# LEDs.net
KiCad netlist of a schematic drawn in Altium Designer
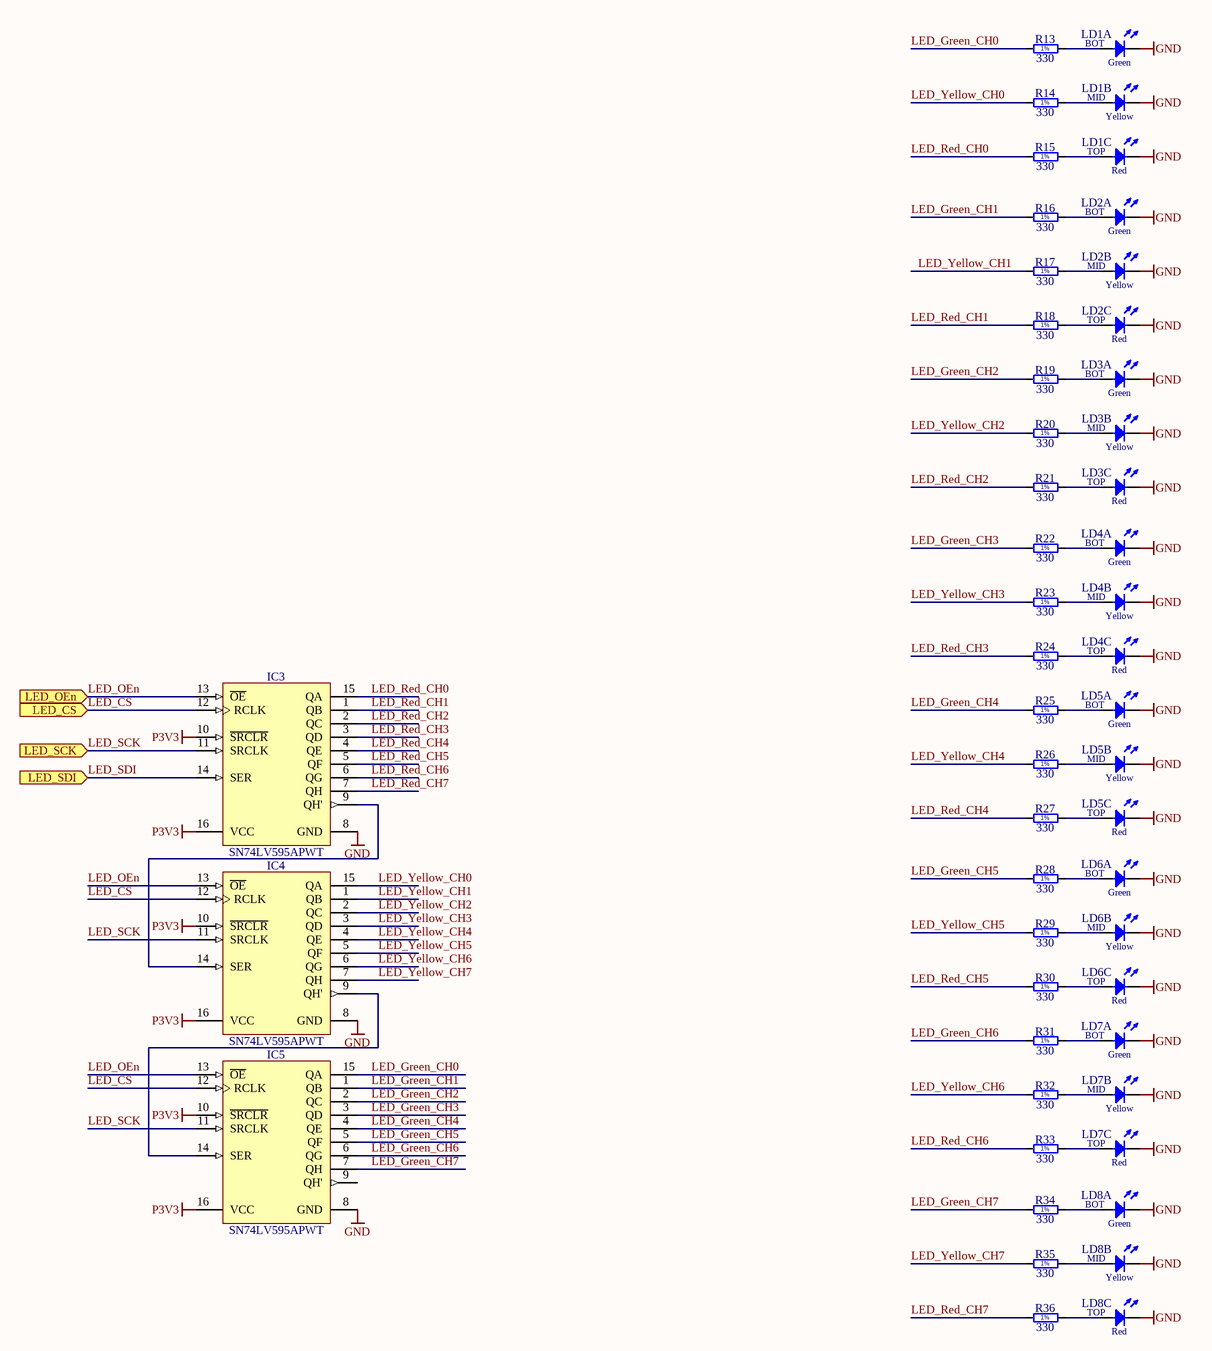
[diagram p0: LEDs.SchDoc]

(export (version "E")
  (design (tool "Eeschema 10.0.6"))
  (components
    (comp (ref "IC3")
      (value "SN74LV595APWT")
      (footprint "SOP65P640X120-16N")
      (description "8-Bit Shift Register With 3-State Output Register")
      (fields (field (name "MANUFACTURER") "TEXAS INSTRUMENTS") (field (name "AUTHOR") "CERN DEM JLC"))
      (libsource (lib "ICs And Semiconductors") (part "74595"))
    )
    (comp (ref "IC4")
      (value "SN74LV595APWT")
      (footprint "SOP65P640X120-16N")
      (description "8-Bit Shift Register With 3-State Output Register")
      (fields (field (name "MANUFACTURER") "TEXAS INSTRUMENTS") (field (name "AUTHOR") "CERN DEM JLC"))
      (libsource (lib "ICs And Semiconductors") (part "74595"))
    )
    (comp (ref "IC5")
      (value "SN74LV595APWT")
      (footprint "SOP65P640X120-16N")
      (description "8-Bit Shift Register With 3-State Output Register")
      (fields (field (name "MANUFACTURER") "TEXAS INSTRUMENTS") (field (name "AUTHOR") "CERN DEM JLC"))
      (libsource (lib "ICs And Semiconductors") (part "74595"))
    )
    (comp (ref "LD1")
      (value "Red/Yellow/Green")
      (footprint "LED_MENTOR_1882.2781")
      (description "LED x3 G-1C2A-BOT_Y-3C4A_R-5C6A-TOP")
      (fields
        (field (name "PART NUMBER") "LED_MENTOR_1882.2781")
        (field (name "MANUFACTURER") "MENTOR")
        (field (name "AUTHOR") "CERN DEM JLC")
      )
      (libsource (lib "ICs And Semiconductors") (part "LED x3 G-1C2A-BOT_Y-3C4A_R-5C6A-TOP"))
    )
    (comp (ref "LD2")
      (value "Red/Yellow/Green")
      (footprint "LED_MENTOR_1882.2781")
      (description "LED x3 G-1C2A-BOT_Y-3C4A_R-5C6A-TOP")
      (fields
        (field (name "PART NUMBER") "LED_MENTOR_1882.2781")
        (field (name "MANUFACTURER") "MENTOR")
        (field (name "AUTHOR") "CERN DEM JLC")
      )
      (libsource (lib "ICs And Semiconductors") (part "LED x3 G-1C2A-BOT_Y-3C4A_R-5C6A-TOP"))
    )
    (comp (ref "LD3")
      (value "Red/Yellow/Green")
      (footprint "LED_MENTOR_1882.2781")
      (description "LED x3 G-1C2A-BOT_Y-3C4A_R-5C6A-TOP")
      (fields
        (field (name "PART NUMBER") "LED_MENTOR_1882.2781")
        (field (name "MANUFACTURER") "MENTOR")
        (field (name "AUTHOR") "CERN DEM JLC")
      )
      (libsource (lib "ICs And Semiconductors") (part "LED x3 G-1C2A-BOT_Y-3C4A_R-5C6A-TOP"))
    )
    (comp (ref "LD4")
      (value "Red/Yellow/Green")
      (footprint "LED_MENTOR_1882.2781")
      (description "LED x3 G-1C2A-BOT_Y-3C4A_R-5C6A-TOP")
      (fields
        (field (name "PART NUMBER") "LED_MENTOR_1882.2781")
        (field (name "MANUFACTURER") "MENTOR")
        (field (name "AUTHOR") "CERN DEM JLC")
      )
      (libsource (lib "ICs And Semiconductors") (part "LED x3 G-1C2A-BOT_Y-3C4A_R-5C6A-TOP"))
    )
    (comp (ref "LD5")
      (value "Red/Yellow/Green")
      (footprint "LED_MENTOR_1882.2781")
      (description "LED x3 G-1C2A-BOT_Y-3C4A_R-5C6A-TOP")
      (fields
        (field (name "PART NUMBER") "LED_MENTOR_1882.2781")
        (field (name "MANUFACTURER") "MENTOR")
        (field (name "AUTHOR") "CERN DEM JLC")
      )
      (libsource (lib "ICs And Semiconductors") (part "LED x3 G-1C2A-BOT_Y-3C4A_R-5C6A-TOP"))
    )
    (comp (ref "LD6")
      (value "Red/Yellow/Green")
      (footprint "LED_MENTOR_1882.2781")
      (description "LED x3 G-1C2A-BOT_Y-3C4A_R-5C6A-TOP")
      (fields
        (field (name "PART NUMBER") "LED_MENTOR_1882.2781")
        (field (name "MANUFACTURER") "MENTOR")
        (field (name "AUTHOR") "CERN DEM JLC")
      )
      (libsource (lib "ICs And Semiconductors") (part "LED x3 G-1C2A-BOT_Y-3C4A_R-5C6A-TOP"))
    )
    (comp (ref "LD7")
      (value "Red/Yellow/Green")
      (footprint "LED_MENTOR_1882.2781")
      (description "LED x3 G-1C2A-BOT_Y-3C4A_R-5C6A-TOP")
      (fields
        (field (name "PART NUMBER") "LED_MENTOR_1882.2781")
        (field (name "MANUFACTURER") "MENTOR")
        (field (name "AUTHOR") "CERN DEM JLC")
      )
      (libsource (lib "ICs And Semiconductors") (part "LED x3 G-1C2A-BOT_Y-3C4A_R-5C6A-TOP"))
    )
    (comp (ref "LD8")
      (value "Red/Yellow/Green")
      (footprint "LED_MENTOR_1882.2781")
      (description "LED x3 G-1C2A-BOT_Y-3C4A_R-5C6A-TOP")
      (fields
        (field (name "PART NUMBER") "LED_MENTOR_1882.2781")
        (field (name "MANUFACTURER") "MENTOR")
        (field (name "AUTHOR") "CERN DEM JLC")
      )
      (libsource (lib "ICs And Semiconductors") (part "LED x3 G-1C2A-BOT_Y-3C4A_R-5C6A-TOP"))
    )
    (comp (ref "R13")
      (value "330")
      (footprint "RESC1608X55N")
      (description "Resistor - 1%")
      (fields
        (field (name "PART NUMBER") "R0603_330R_1%_0.1W_100PPM")
        (field (name "POWER") "0.1W")
        (field (name "AUTHOR") "CERN DEM JLC")
      )
      (libsource (lib "Resistors") (part "Resistor - 1%"))
    )
    (comp (ref "R14")
      (value "330")
      (footprint "RESC1608X55N")
      (description "Resistor - 1%")
      (fields
        (field (name "PART NUMBER") "R0603_330R_1%_0.1W_100PPM")
        (field (name "POWER") "0.1W")
        (field (name "AUTHOR") "CERN DEM JLC")
      )
      (libsource (lib "Resistors") (part "Resistor - 1%"))
    )
    (comp (ref "R15")
      (value "330")
      (footprint "RESC1608X55N")
      (description "Resistor - 1%")
      (fields
        (field (name "PART NUMBER") "R0603_330R_1%_0.1W_100PPM")
        (field (name "POWER") "0.1W")
        (field (name "AUTHOR") "CERN DEM JLC")
      )
      (libsource (lib "Resistors") (part "Resistor - 1%"))
    )
    (comp (ref "R16")
      (value "330")
      (footprint "RESC1608X55N")
      (description "Resistor - 1%")
      (fields
        (field (name "PART NUMBER") "R0603_330R_1%_0.1W_100PPM")
        (field (name "POWER") "0.1W")
        (field (name "AUTHOR") "CERN DEM JLC")
      )
      (libsource (lib "Resistors") (part "Resistor - 1%"))
    )
    (comp (ref "R17")
      (value "330")
      (footprint "RESC1608X55N")
      (description "Resistor - 1%")
      (fields
        (field (name "PART NUMBER") "R0603_330R_1%_0.1W_100PPM")
        (field (name "POWER") "0.1W")
        (field (name "AUTHOR") "CERN DEM JLC")
      )
      (libsource (lib "Resistors") (part "Resistor - 1%"))
    )
    (comp (ref "R18")
      (value "330")
      (footprint "RESC1608X55N")
      (description "Resistor - 1%")
      (fields
        (field (name "PART NUMBER") "R0603_330R_1%_0.1W_100PPM")
        (field (name "POWER") "0.1W")
        (field (name "AUTHOR") "CERN DEM JLC")
      )
      (libsource (lib "Resistors") (part "Resistor - 1%"))
    )
    (comp (ref "R19")
      (value "330")
      (footprint "RESC1608X55N")
      (description "Resistor - 1%")
      (fields
        (field (name "PART NUMBER") "R0603_330R_1%_0.1W_100PPM")
        (field (name "POWER") "0.1W")
        (field (name "AUTHOR") "CERN DEM JLC")
      )
      (libsource (lib "Resistors") (part "Resistor - 1%"))
    )
    (comp (ref "R20")
      (value "330")
      (footprint "RESC1608X55N")
      (description "Resistor - 1%")
      (fields
        (field (name "PART NUMBER") "R0603_330R_1%_0.1W_100PPM")
        (field (name "POWER") "0.1W")
        (field (name "AUTHOR") "CERN DEM JLC")
      )
      (libsource (lib "Resistors") (part "Resistor - 1%"))
    )
    (comp (ref "R21")
      (value "330")
      (footprint "RESC1608X55N")
      (description "Resistor - 1%")
      (fields
        (field (name "PART NUMBER") "R0603_330R_1%_0.1W_100PPM")
        (field (name "POWER") "0.1W")
        (field (name "AUTHOR") "CERN DEM JLC")
      )
      (libsource (lib "Resistors") (part "Resistor - 1%"))
    )
    (comp (ref "R22")
      (value "330")
      (footprint "RESC1608X55N")
      (description "Resistor - 1%")
      (fields
        (field (name "PART NUMBER") "R0603_330R_1%_0.1W_100PPM")
        (field (name "POWER") "0.1W")
        (field (name "AUTHOR") "CERN DEM JLC")
      )
      (libsource (lib "Resistors") (part "Resistor - 1%"))
    )
    (comp (ref "R23")
      (value "330")
      (footprint "RESC1608X55N")
      (description "Resistor - 1%")
      (fields
        (field (name "PART NUMBER") "R0603_330R_1%_0.1W_100PPM")
        (field (name "POWER") "0.1W")
        (field (name "AUTHOR") "CERN DEM JLC")
      )
      (libsource (lib "Resistors") (part "Resistor - 1%"))
    )
    (comp (ref "R24")
      (value "330")
      (footprint "RESC1608X55N")
      (description "Resistor - 1%")
      (fields
        (field (name "PART NUMBER") "R0603_330R_1%_0.1W_100PPM")
        (field (name "POWER") "0.1W")
        (field (name "AUTHOR") "CERN DEM JLC")
      )
      (libsource (lib "Resistors") (part "Resistor - 1%"))
    )
    (comp (ref "R25")
      (value "330")
      (footprint "RESC1608X55N")
      (description "Resistor - 1%")
      (fields
        (field (name "PART NUMBER") "R0603_330R_1%_0.1W_100PPM")
        (field (name "POWER") "0.1W")
        (field (name "AUTHOR") "CERN DEM JLC")
      )
      (libsource (lib "Resistors") (part "Resistor - 1%"))
    )
    (comp (ref "R26")
      (value "330")
      (footprint "RESC1608X55N")
      (description "Resistor - 1%")
      (fields
        (field (name "PART NUMBER") "R0603_330R_1%_0.1W_100PPM")
        (field (name "POWER") "0.1W")
        (field (name "AUTHOR") "CERN DEM JLC")
      )
      (libsource (lib "Resistors") (part "Resistor - 1%"))
    )
    (comp (ref "R27")
      (value "330")
      (footprint "RESC1608X55N")
      (description "Resistor - 1%")
      (fields
        (field (name "PART NUMBER") "R0603_330R_1%_0.1W_100PPM")
        (field (name "POWER") "0.1W")
        (field (name "AUTHOR") "CERN DEM JLC")
      )
      (libsource (lib "Resistors") (part "Resistor - 1%"))
    )
    (comp (ref "R28")
      (value "330")
      (footprint "RESC1608X55N")
      (description "Resistor - 1%")
      (fields
        (field (name "PART NUMBER") "R0603_330R_1%_0.1W_100PPM")
        (field (name "POWER") "0.1W")
        (field (name "AUTHOR") "CERN DEM JLC")
      )
      (libsource (lib "Resistors") (part "Resistor - 1%"))
    )
    (comp (ref "R29")
      (value "330")
      (footprint "RESC1608X55N")
      (description "Resistor - 1%")
      (fields
        (field (name "PART NUMBER") "R0603_330R_1%_0.1W_100PPM")
        (field (name "POWER") "0.1W")
        (field (name "AUTHOR") "CERN DEM JLC")
      )
      (libsource (lib "Resistors") (part "Resistor - 1%"))
    )
    (comp (ref "R30")
      (value "330")
      (footprint "RESC1608X55N")
      (description "Resistor - 1%")
      (fields
        (field (name "PART NUMBER") "R0603_330R_1%_0.1W_100PPM")
        (field (name "POWER") "0.1W")
        (field (name "AUTHOR") "CERN DEM JLC")
      )
      (libsource (lib "Resistors") (part "Resistor - 1%"))
    )
    (comp (ref "R31")
      (value "330")
      (footprint "RESC1608X55N")
      (description "Resistor - 1%")
      (fields
        (field (name "PART NUMBER") "R0603_330R_1%_0.1W_100PPM")
        (field (name "POWER") "0.1W")
        (field (name "AUTHOR") "CERN DEM JLC")
      )
      (libsource (lib "Resistors") (part "Resistor - 1%"))
    )
    (comp (ref "R32")
      (value "330")
      (footprint "RESC1608X55N")
      (description "Resistor - 1%")
      (fields
        (field (name "PART NUMBER") "R0603_330R_1%_0.1W_100PPM")
        (field (name "POWER") "0.1W")
        (field (name "AUTHOR") "CERN DEM JLC")
      )
      (libsource (lib "Resistors") (part "Resistor - 1%"))
    )
    (comp (ref "R33")
      (value "330")
      (footprint "RESC1608X55N")
      (description "Resistor - 1%")
      (fields
        (field (name "PART NUMBER") "R0603_330R_1%_0.1W_100PPM")
        (field (name "POWER") "0.1W")
        (field (name "AUTHOR") "CERN DEM JLC")
      )
      (libsource (lib "Resistors") (part "Resistor - 1%"))
    )
    (comp (ref "R34")
      (value "330")
      (footprint "RESC1608X55N")
      (description "Resistor - 1%")
      (fields
        (field (name "PART NUMBER") "R0603_330R_1%_0.1W_100PPM")
        (field (name "POWER") "0.1W")
        (field (name "AUTHOR") "CERN DEM JLC")
      )
      (libsource (lib "Resistors") (part "Resistor - 1%"))
    )
    (comp (ref "R35")
      (value "330")
      (footprint "RESC1608X55N")
      (description "Resistor - 1%")
      (fields
        (field (name "PART NUMBER") "R0603_330R_1%_0.1W_100PPM")
        (field (name "POWER") "0.1W")
        (field (name "AUTHOR") "CERN DEM JLC")
      )
      (libsource (lib "Resistors") (part "Resistor - 1%"))
    )
    (comp (ref "R36")
      (value "330")
      (footprint "RESC1608X55N")
      (description "Resistor - 1%")
      (fields
        (field (name "PART NUMBER") "R0603_330R_1%_0.1W_100PPM")
        (field (name "POWER") "0.1W")
        (field (name "AUTHOR") "CERN DEM JLC")
      )
      (libsource (lib "Resistors") (part "Resistor - 1%"))
    )
  )
  (nets
    (net (code "1") (name "/LED_CS") (class "Default")
      (node (ref "IC3") (pin "12") (pinfunction "RCLK_12") (pintype "input"))
      (node (ref "IC4") (pin "12") (pinfunction "RCLK_12") (pintype "input"))
      (node (ref "IC5") (pin "12") (pinfunction "RCLK_12") (pintype "input"))
    )
    (net (code "2") (name "/LED_Green_CH0") (class "Default")
      (node (ref "IC5") (pin "15") (pinfunction "QA_15") (pintype "tri_state"))
      (node (ref "R13") (pin "1") (pinfunction "1_1") (pintype "passive"))
    )
    (net (code "3") (name "/LED_Green_CH1") (class "Default")
      (node (ref "IC5") (pin "1") (pinfunction "QB_1") (pintype "tri_state"))
      (node (ref "R16") (pin "1") (pinfunction "1_1") (pintype "passive"))
    )
    (net (code "4") (name "/LED_Green_CH2") (class "Default")
      (node (ref "IC5") (pin "2") (pinfunction "QC_2") (pintype "tri_state"))
      (node (ref "R19") (pin "1") (pinfunction "1_1") (pintype "passive"))
    )
    (net (code "5") (name "/LED_Green_CH3") (class "Default")
      (node (ref "IC5") (pin "3") (pinfunction "QD_3") (pintype "tri_state"))
      (node (ref "R22") (pin "1") (pinfunction "1_1") (pintype "passive"))
    )
    (net (code "6") (name "/LED_Green_CH4") (class "Default")
      (node (ref "IC5") (pin "4") (pinfunction "QE_4") (pintype "tri_state"))
      (node (ref "R25") (pin "1") (pinfunction "1_1") (pintype "passive"))
    )
    (net (code "7") (name "/LED_Green_CH5") (class "Default")
      (node (ref "IC5") (pin "5") (pinfunction "QF_5") (pintype "tri_state"))
      (node (ref "R28") (pin "1") (pinfunction "1_1") (pintype "passive"))
    )
    (net (code "8") (name "/LED_Green_CH6") (class "Default")
      (node (ref "IC5") (pin "6") (pinfunction "QG_6") (pintype "tri_state"))
      (node (ref "R31") (pin "1") (pinfunction "1_1") (pintype "passive"))
    )
    (net (code "9") (name "/LED_Green_CH7") (class "Default")
      (node (ref "IC5") (pin "7") (pinfunction "QH_7") (pintype "tri_state"))
      (node (ref "R34") (pin "1") (pinfunction "1_1") (pintype "passive"))
    )
    (net (code "10") (name "/LED_OEn") (class "Default")
      (node (ref "IC3") (pin "13") (pinfunction "~{OE}_13") (pintype "input"))
      (node (ref "IC4") (pin "13") (pinfunction "~{OE}_13") (pintype "input"))
      (node (ref "IC5") (pin "13") (pinfunction "~{OE}_13") (pintype "input"))
    )
    (net (code "11") (name "/LED_Red_CH0") (class "Default")
      (node (ref "IC3") (pin "15") (pinfunction "QA_15") (pintype "tri_state"))
      (node (ref "R15") (pin "1") (pinfunction "1_1") (pintype "passive"))
    )
    (net (code "12") (name "/LED_Red_CH1") (class "Default")
      (node (ref "IC3") (pin "1") (pinfunction "QB_1") (pintype "tri_state"))
      (node (ref "R18") (pin "1") (pinfunction "1_1") (pintype "passive"))
    )
    (net (code "13") (name "/LED_Red_CH2") (class "Default")
      (node (ref "IC3") (pin "2") (pinfunction "QC_2") (pintype "tri_state"))
      (node (ref "R21") (pin "1") (pinfunction "1_1") (pintype "passive"))
    )
    (net (code "14") (name "/LED_Red_CH3") (class "Default")
      (node (ref "IC3") (pin "3") (pinfunction "QD_3") (pintype "tri_state"))
      (node (ref "R24") (pin "1") (pinfunction "1_1") (pintype "passive"))
    )
    (net (code "15") (name "/LED_Red_CH4") (class "Default")
      (node (ref "IC3") (pin "4") (pinfunction "QE_4") (pintype "tri_state"))
      (node (ref "R27") (pin "1") (pinfunction "1_1") (pintype "passive"))
    )
    (net (code "16") (name "/LED_Red_CH5") (class "Default")
      (node (ref "IC3") (pin "5") (pinfunction "QF_5") (pintype "tri_state"))
      (node (ref "R30") (pin "1") (pinfunction "1_1") (pintype "passive"))
    )
    (net (code "17") (name "/LED_Red_CH6") (class "Default")
      (node (ref "IC3") (pin "6") (pinfunction "QG_6") (pintype "tri_state"))
      (node (ref "R33") (pin "1") (pinfunction "1_1") (pintype "passive"))
    )
    (net (code "18") (name "/LED_Red_CH7") (class "Default")
      (node (ref "IC3") (pin "7") (pinfunction "QH_7") (pintype "tri_state"))
      (node (ref "R36") (pin "1") (pinfunction "1_1") (pintype "passive"))
    )
    (net (code "19") (name "/LED_SCK") (class "Default")
      (node (ref "IC3") (pin "11") (pinfunction "SRCLK_11") (pintype "input"))
      (node (ref "IC4") (pin "11") (pinfunction "SRCLK_11") (pintype "input"))
      (node (ref "IC5") (pin "11") (pinfunction "SRCLK_11") (pintype "input"))
    )
    (net (code "20") (name "/LED_SDI") (class "Default")
      (node (ref "IC3") (pin "14") (pinfunction "SER_14") (pintype "input"))
    )
    (net (code "21") (name "/LED_Yellow_CH0") (class "Default")
      (node (ref "IC4") (pin "15") (pinfunction "QA_15") (pintype "tri_state"))
      (node (ref "R14") (pin "1") (pinfunction "1_1") (pintype "passive"))
    )
    (net (code "22") (name "/LED_Yellow_CH1") (class "Default")
      (node (ref "IC4") (pin "1") (pinfunction "QB_1") (pintype "tri_state"))
      (node (ref "R17") (pin "1") (pinfunction "1_1") (pintype "passive"))
    )
    (net (code "23") (name "/LED_Yellow_CH2") (class "Default")
      (node (ref "IC4") (pin "2") (pinfunction "QC_2") (pintype "tri_state"))
      (node (ref "R20") (pin "1") (pinfunction "1_1") (pintype "passive"))
    )
    (net (code "24") (name "/LED_Yellow_CH3") (class "Default")
      (node (ref "IC4") (pin "3") (pinfunction "QD_3") (pintype "tri_state"))
      (node (ref "R23") (pin "1") (pinfunction "1_1") (pintype "passive"))
    )
    (net (code "25") (name "/LED_Yellow_CH4") (class "Default")
      (node (ref "IC4") (pin "4") (pinfunction "QE_4") (pintype "tri_state"))
      (node (ref "R26") (pin "1") (pinfunction "1_1") (pintype "passive"))
    )
    (net (code "26") (name "/LED_Yellow_CH5") (class "Default")
      (node (ref "IC4") (pin "5") (pinfunction "QF_5") (pintype "tri_state"))
      (node (ref "R29") (pin "1") (pinfunction "1_1") (pintype "passive"))
    )
    (net (code "27") (name "/LED_Yellow_CH6") (class "Default")
      (node (ref "IC4") (pin "6") (pinfunction "QG_6") (pintype "tri_state"))
      (node (ref "R32") (pin "1") (pinfunction "1_1") (pintype "passive"))
    )
    (net (code "28") (name "/LED_Yellow_CH7") (class "Default")
      (node (ref "IC4") (pin "7") (pinfunction "QH_7") (pintype "tri_state"))
      (node (ref "R35") (pin "1") (pinfunction "1_1") (pintype "passive"))
    )
    (net (code "29") (name "GND") (class "Default")
      (node (ref "IC3") (pin "8") (pinfunction "GND_8") (pintype "power_in"))
      (node (ref "IC4") (pin "8") (pinfunction "GND_8") (pintype "power_in"))
      (node (ref "IC5") (pin "8") (pinfunction "GND_8") (pintype "power_in"))
      (node (ref "LD1") (pin "1") (pinfunction "C_1") (pintype "passive"))
      (node (ref "LD1") (pin "3") (pinfunction "C_3") (pintype "passive"))
      (node (ref "LD1") (pin "5") (pinfunction "C_5") (pintype "passive"))
      (node (ref "LD2") (pin "1") (pinfunction "C_1") (pintype "passive"))
      (node (ref "LD2") (pin "3") (pinfunction "C_3") (pintype "passive"))
      (node (ref "LD2") (pin "5") (pinfunction "C_5") (pintype "passive"))
      (node (ref "LD3") (pin "1") (pinfunction "C_1") (pintype "passive"))
      (node (ref "LD3") (pin "3") (pinfunction "C_3") (pintype "passive"))
      (node (ref "LD3") (pin "5") (pinfunction "C_5") (pintype "passive"))
      (node (ref "LD4") (pin "1") (pinfunction "C_1") (pintype "passive"))
      (node (ref "LD4") (pin "3") (pinfunction "C_3") (pintype "passive"))
      (node (ref "LD4") (pin "5") (pinfunction "C_5") (pintype "passive"))
      (node (ref "LD5") (pin "1") (pinfunction "C_1") (pintype "passive"))
      (node (ref "LD5") (pin "3") (pinfunction "C_3") (pintype "passive"))
      (node (ref "LD5") (pin "5") (pinfunction "C_5") (pintype "passive"))
      (node (ref "LD6") (pin "1") (pinfunction "C_1") (pintype "passive"))
      (node (ref "LD6") (pin "3") (pinfunction "C_3") (pintype "passive"))
      (node (ref "LD6") (pin "5") (pinfunction "C_5") (pintype "passive"))
      (node (ref "LD7") (pin "1") (pinfunction "C_1") (pintype "passive"))
      (node (ref "LD7") (pin "3") (pinfunction "C_3") (pintype "passive"))
      (node (ref "LD7") (pin "5") (pinfunction "C_5") (pintype "passive"))
      (node (ref "LD8") (pin "1") (pinfunction "C_1") (pintype "passive"))
      (node (ref "LD8") (pin "3") (pinfunction "C_3") (pintype "passive"))
      (node (ref "LD8") (pin "5") (pinfunction "C_5") (pintype "passive"))
    )
    (net (code "30") (name "Net-(IC3-QH')") (class "Default")
      (node (ref "IC3") (pin "9") (pinfunction "QH'_9") (pintype "output"))
      (node (ref "IC4") (pin "14") (pinfunction "SER_14") (pintype "input"))
    )
    (net (code "31") (name "Net-(IC4-QH')") (class "Default")
      (node (ref "IC4") (pin "9") (pinfunction "QH'_9") (pintype "output"))
      (node (ref "IC5") (pin "14") (pinfunction "SER_14") (pintype "input"))
    )
    (net (code "32") (name "Net-(LD1A-A)") (class "Default")
      (node (ref "LD1") (pin "2") (pinfunction "A_2") (pintype "passive"))
      (node (ref "R13") (pin "2") (pinfunction "2_2") (pintype "passive"))
    )
    (net (code "33") (name "Net-(LD1B-A)") (class "Default")
      (node (ref "LD1") (pin "4") (pinfunction "A_4") (pintype "passive"))
      (node (ref "R14") (pin "2") (pinfunction "2_2") (pintype "passive"))
    )
    (net (code "34") (name "Net-(LD1C-A)") (class "Default")
      (node (ref "LD1") (pin "6") (pinfunction "A_6") (pintype "passive"))
      (node (ref "R15") (pin "2") (pinfunction "2_2") (pintype "passive"))
    )
    (net (code "35") (name "Net-(LD2A-A)") (class "Default")
      (node (ref "LD2") (pin "2") (pinfunction "A_2") (pintype "passive"))
      (node (ref "R16") (pin "2") (pinfunction "2_2") (pintype "passive"))
    )
    (net (code "36") (name "Net-(LD2B-A)") (class "Default")
      (node (ref "LD2") (pin "4") (pinfunction "A_4") (pintype "passive"))
      (node (ref "R17") (pin "2") (pinfunction "2_2") (pintype "passive"))
    )
    (net (code "37") (name "Net-(LD2C-A)") (class "Default")
      (node (ref "LD2") (pin "6") (pinfunction "A_6") (pintype "passive"))
      (node (ref "R18") (pin "2") (pinfunction "2_2") (pintype "passive"))
    )
    (net (code "38") (name "Net-(LD3A-A)") (class "Default")
      (node (ref "LD3") (pin "2") (pinfunction "A_2") (pintype "passive"))
      (node (ref "R19") (pin "2") (pinfunction "2_2") (pintype "passive"))
    )
    (net (code "39") (name "Net-(LD3B-A)") (class "Default")
      (node (ref "LD3") (pin "4") (pinfunction "A_4") (pintype "passive"))
      (node (ref "R20") (pin "2") (pinfunction "2_2") (pintype "passive"))
    )
    (net (code "40") (name "Net-(LD3C-A)") (class "Default")
      (node (ref "LD3") (pin "6") (pinfunction "A_6") (pintype "passive"))
      (node (ref "R21") (pin "2") (pinfunction "2_2") (pintype "passive"))
    )
    (net (code "41") (name "Net-(LD4A-A)") (class "Default")
      (node (ref "LD4") (pin "2") (pinfunction "A_2") (pintype "passive"))
      (node (ref "R22") (pin "2") (pinfunction "2_2") (pintype "passive"))
    )
    (net (code "42") (name "Net-(LD4B-A)") (class "Default")
      (node (ref "LD4") (pin "4") (pinfunction "A_4") (pintype "passive"))
      (node (ref "R23") (pin "2") (pinfunction "2_2") (pintype "passive"))
    )
    (net (code "43") (name "Net-(LD4C-A)") (class "Default")
      (node (ref "LD4") (pin "6") (pinfunction "A_6") (pintype "passive"))
      (node (ref "R24") (pin "2") (pinfunction "2_2") (pintype "passive"))
    )
    (net (code "44") (name "Net-(LD5A-A)") (class "Default")
      (node (ref "LD5") (pin "2") (pinfunction "A_2") (pintype "passive"))
      (node (ref "R25") (pin "2") (pinfunction "2_2") (pintype "passive"))
    )
    (net (code "45") (name "Net-(LD5B-A)") (class "Default")
      (node (ref "LD5") (pin "4") (pinfunction "A_4") (pintype "passive"))
      (node (ref "R26") (pin "2") (pinfunction "2_2") (pintype "passive"))
    )
    (net (code "46") (name "Net-(LD5C-A)") (class "Default")
      (node (ref "LD5") (pin "6") (pinfunction "A_6") (pintype "passive"))
      (node (ref "R27") (pin "2") (pinfunction "2_2") (pintype "passive"))
    )
    (net (code "47") (name "Net-(LD6A-A)") (class "Default")
      (node (ref "LD6") (pin "2") (pinfunction "A_2") (pintype "passive"))
      (node (ref "R28") (pin "2") (pinfunction "2_2") (pintype "passive"))
    )
    (net (code "48") (name "Net-(LD6B-A)") (class "Default")
      (node (ref "LD6") (pin "4") (pinfunction "A_4") (pintype "passive"))
      (node (ref "R29") (pin "2") (pinfunction "2_2") (pintype "passive"))
    )
    (net (code "49") (name "Net-(LD6C-A)") (class "Default")
      (node (ref "LD6") (pin "6") (pinfunction "A_6") (pintype "passive"))
      (node (ref "R30") (pin "2") (pinfunction "2_2") (pintype "passive"))
    )
    (net (code "50") (name "Net-(LD7A-A)") (class "Default")
      (node (ref "LD7") (pin "2") (pinfunction "A_2") (pintype "passive"))
      (node (ref "R31") (pin "2") (pinfunction "2_2") (pintype "passive"))
    )
    (net (code "51") (name "Net-(LD7B-A)") (class "Default")
      (node (ref "LD7") (pin "4") (pinfunction "A_4") (pintype "passive"))
      (node (ref "R32") (pin "2") (pinfunction "2_2") (pintype "passive"))
    )
    (net (code "52") (name "Net-(LD7C-A)") (class "Default")
      (node (ref "LD7") (pin "6") (pinfunction "A_6") (pintype "passive"))
      (node (ref "R33") (pin "2") (pinfunction "2_2") (pintype "passive"))
    )
    (net (code "53") (name "Net-(LD8A-A)") (class "Default")
      (node (ref "LD8") (pin "2") (pinfunction "A_2") (pintype "passive"))
      (node (ref "R34") (pin "2") (pinfunction "2_2") (pintype "passive"))
    )
    (net (code "54") (name "Net-(LD8B-A)") (class "Default")
      (node (ref "LD8") (pin "4") (pinfunction "A_4") (pintype "passive"))
      (node (ref "R35") (pin "2") (pinfunction "2_2") (pintype "passive"))
    )
    (net (code "55") (name "Net-(LD8C-A)") (class "Default")
      (node (ref "LD8") (pin "6") (pinfunction "A_6") (pintype "passive"))
      (node (ref "R36") (pin "2") (pinfunction "2_2") (pintype "passive"))
    )
    (net (code "56") (name "P3V3") (class "Default")
      (node (ref "IC3") (pin "10") (pinfunction "~{SRCLR}_10") (pintype "input"))
      (node (ref "IC3") (pin "16") (pinfunction "VCC_16") (pintype "power_in"))
      (node (ref "IC4") (pin "10") (pinfunction "~{SRCLR}_10") (pintype "input"))
      (node (ref "IC4") (pin "16") (pinfunction "VCC_16") (pintype "power_in"))
      (node (ref "IC5") (pin "10") (pinfunction "~{SRCLR}_10") (pintype "input"))
      (node (ref "IC5") (pin "16") (pinfunction "VCC_16") (pintype "power_in"))
    )
    (net (code "57") (name "unconnected-(IC5-QH'-Pad9)") (class "Default")
      (node (ref "IC5") (pin "9") (pinfunction "QH'_9") (pintype "output"))
    )
  )
)
